# RAM_DDR3_2RANK_BGA96.net
KiCad netlist of a schematic drawn in Altium Designer
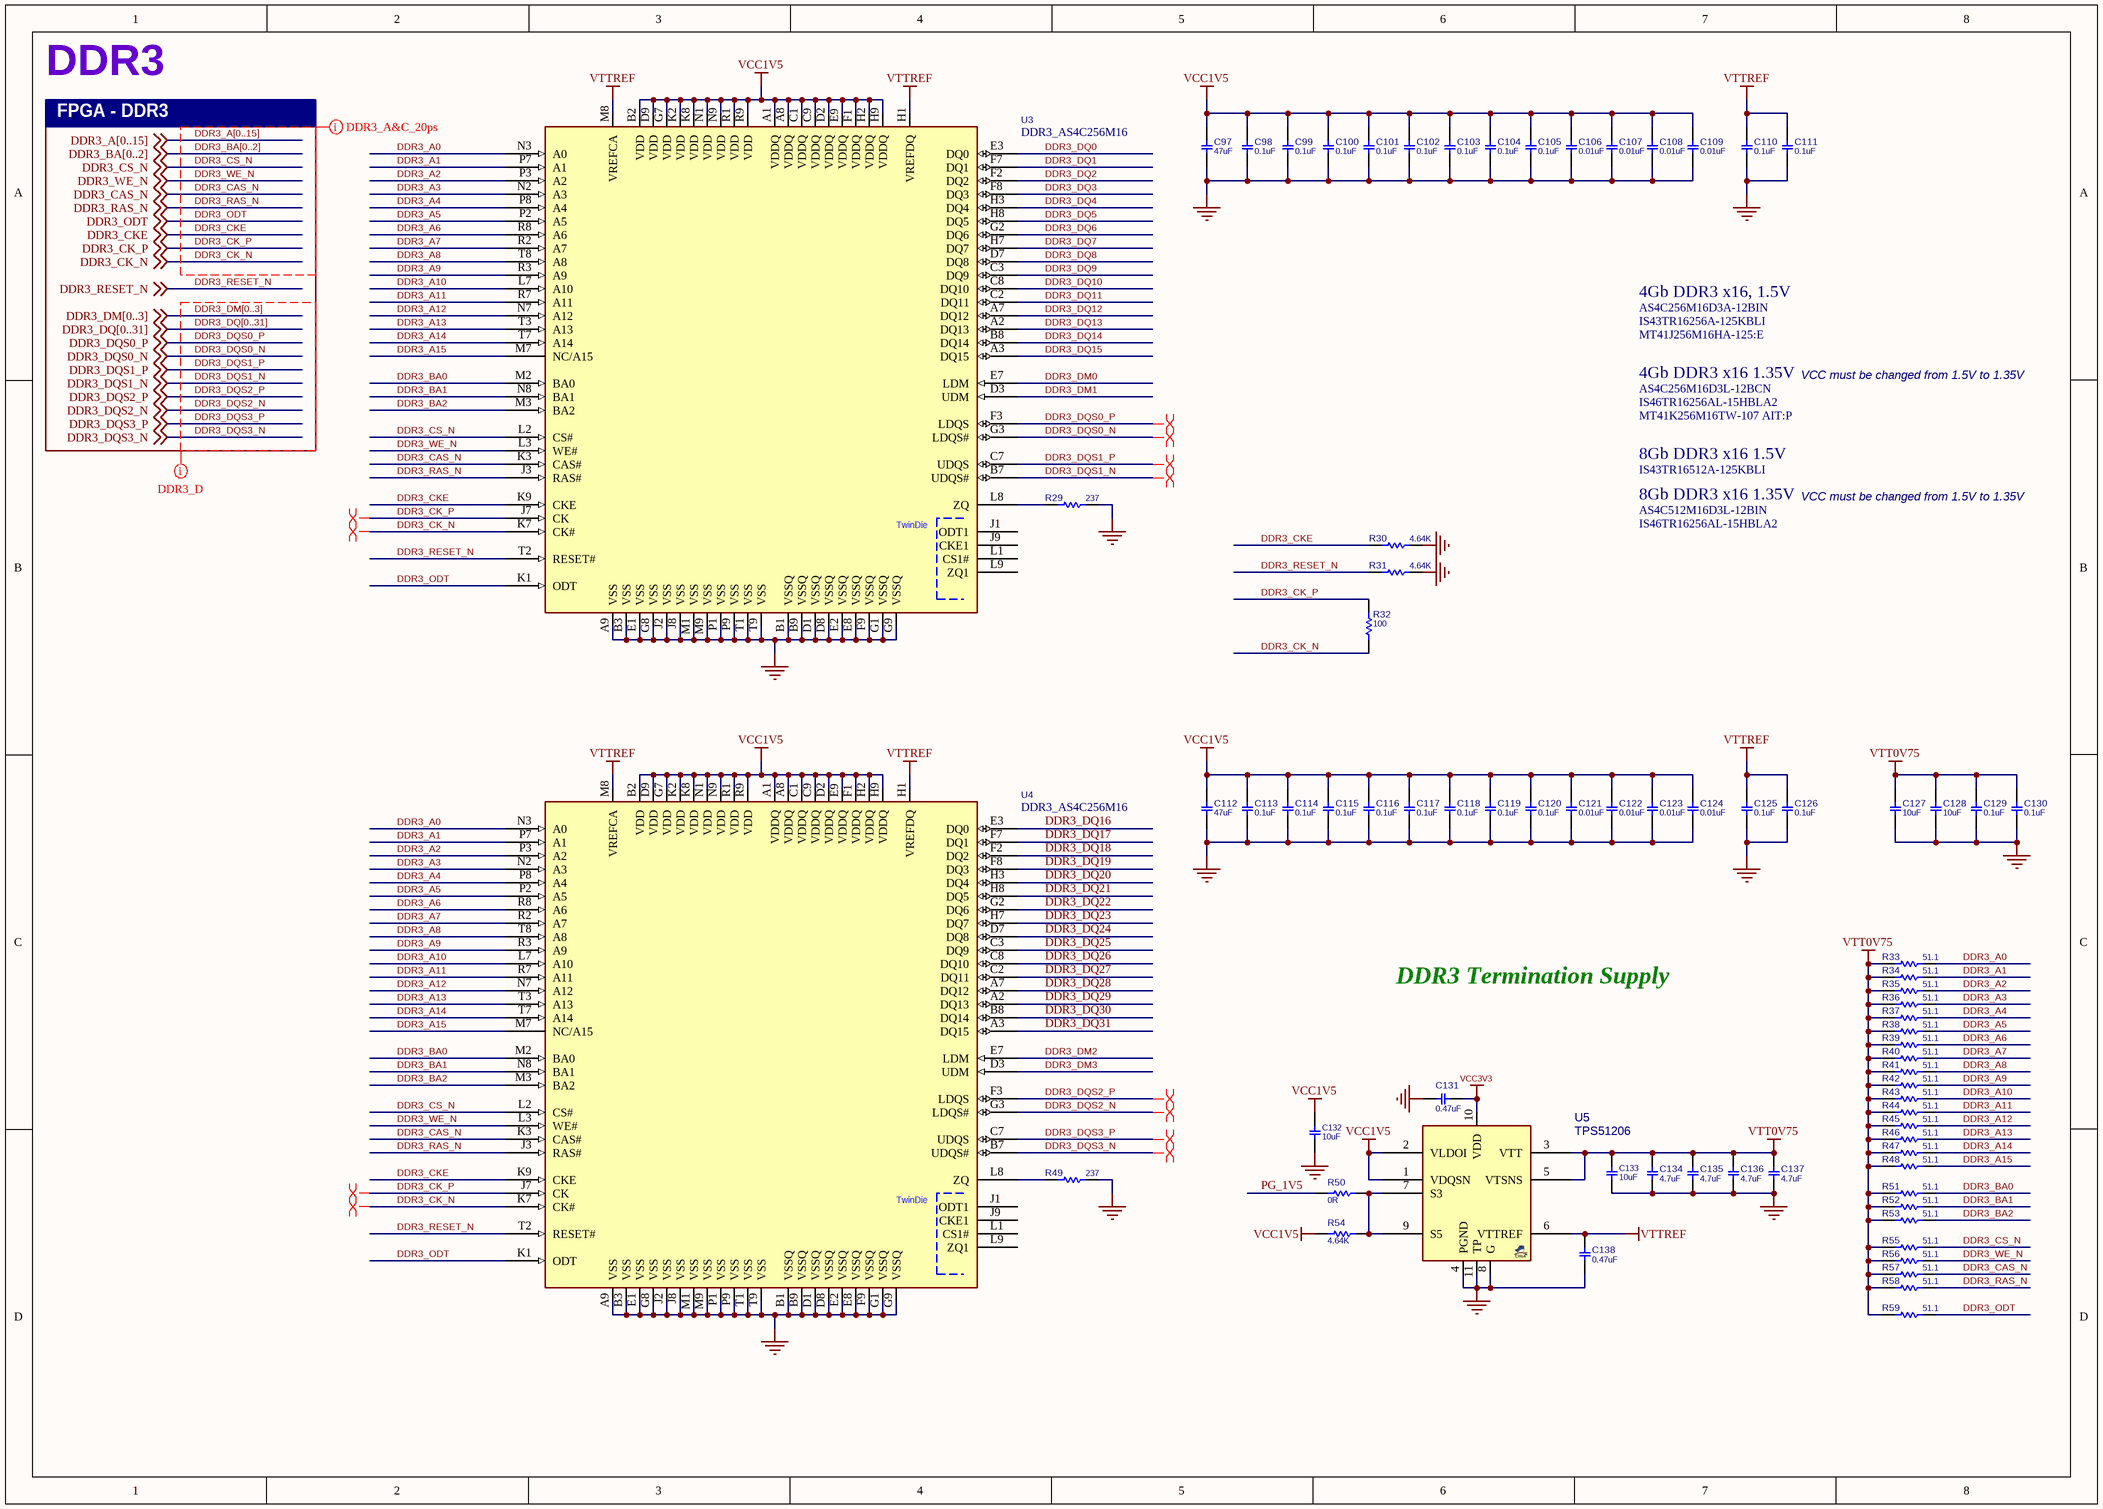
[diagram p0: RAM_DDR3_2RANK_BGA96.SchDoc]

(export (version "E")
  (design (tool "Eeschema 10.0.6"))
  (components
    (comp (ref "C97")
      (value "47uF")
      (footprint "C0805")
      (description "CAP, MLCC, X5R 47uF 16V 10% 1210")
      (fields (field (name "MANF") "Murata") (field (name "MANF_P#") "GRM32ER61C476KE15K"))
      (libsource (lib "mlcc_smd_passive") (part "CAP_SMD_MLCC_47u16V"))
    )
    (comp (ref "C98")
      (value "0.1uF")
      (footprint "C0402")
      (description "CAP, MLCC, 100nF, 50V, X7R, 10%, 0402C")
      (fields (field (name "MANF") "Taiyo Yuden") (field (name "MANF_P#") "UMK105B7104KVHF"))
      (libsource (lib "mlcc_smd_passive") (part "CAP_SMD_MLCC_100n50T"))
    )
    (comp (ref "C99")
      (value "0.1uF")
      (footprint "C0402")
      (description "CAP, MLCC, 100nF, 50V, X7R, 10%, 0402C")
      (fields (field (name "MANF") "Taiyo Yuden") (field (name "MANF_P#") "UMK105B7104KVHF"))
      (libsource (lib "mlcc_smd_passive") (part "CAP_SMD_MLCC_100n50T"))
    )
    (comp (ref "C100")
      (value "0.1uF")
      (footprint "C0402")
      (description "CAP, MLCC, 100nF, 50V, X7R, 10%, 0402C")
      (fields (field (name "MANF") "Taiyo Yuden") (field (name "MANF_P#") "UMK105B7104KVHF"))
      (libsource (lib "mlcc_smd_passive") (part "CAP_SMD_MLCC_100n50T"))
    )
    (comp (ref "C101")
      (value "0.1uF")
      (footprint "C0402")
      (description "CAP, MLCC, 100nF, 50V, X7R, 10%, 0402C")
      (fields (field (name "MANF") "Taiyo Yuden") (field (name "MANF_P#") "UMK105B7104KVHF"))
      (libsource (lib "mlcc_smd_passive") (part "CAP_SMD_MLCC_100n50T"))
    )
    (comp (ref "C102")
      (value "0.1uF")
      (footprint "C0402")
      (description "CAP, MLCC, 100nF, 50V, X7R, 10%, 0402C")
      (fields (field (name "MANF") "Taiyo Yuden") (field (name "MANF_P#") "UMK105B7104KVHF"))
      (libsource (lib "mlcc_smd_passive") (part "CAP_SMD_MLCC_100n50T"))
    )
    (comp (ref "C103")
      (value "0.1uF")
      (footprint "C0402")
      (description "CAP, MLCC, 100nF, 50V, X7R, 10%, 0402C")
      (fields (field (name "MANF") "Taiyo Yuden") (field (name "MANF_P#") "UMK105B7104KVHF"))
      (libsource (lib "mlcc_smd_passive") (part "CAP_SMD_MLCC_100n50T"))
    )
    (comp (ref "C104")
      (value "0.1uF")
      (footprint "C0402")
      (description "CAP, MLCC, 100nF, 50V, X7R, 10%, 0402C")
      (fields (field (name "MANF") "Taiyo Yuden") (field (name "MANF_P#") "UMK105B7104KVHF"))
      (libsource (lib "mlcc_smd_passive") (part "CAP_SMD_MLCC_100n50T"))
    )
    (comp (ref "C105")
      (value "0.1uF")
      (footprint "C0402")
      (description "CAP, MLCC, 100nF, 50V, X7R, 10%, 0402C")
      (fields (field (name "MANF") "Taiyo Yuden") (field (name "MANF_P#") "UMK105B7104KVHF"))
      (libsource (lib "mlcc_smd_passive") (part "CAP_SMD_MLCC_100n50T"))
    )
    (comp (ref "C106")
      (value "0.01uF")
      (footprint "C0402")
      (description "CAP, MLCC, 10nF, 50V, X7R, 10%, 0402C")
      (fields (field (name "MANF") "Murata") (field (name "MANF_P#") "GCM155R71H103KA55D"))
      (libsource (lib "chila_passive") (part "CAP_SMD_MLCC_10n50V"))
    )
    (comp (ref "C107")
      (value "0.01uF")
      (footprint "C0402")
      (description "CAP, MLCC, 10nF, 50V, X7R, 10%, 0402C")
      (fields (field (name "MANF") "Murata") (field (name "MANF_P#") "GCM155R71H103KA55D"))
      (libsource (lib "chila_passive") (part "CAP_SMD_MLCC_10n50V"))
    )
    (comp (ref "C108")
      (value "0.01uF")
      (footprint "C0402")
      (description "CAP, MLCC, 10nF, 50V, X7R, 10%, 0402C")
      (fields (field (name "MANF") "Murata") (field (name "MANF_P#") "GCM155R71H103KA55D"))
      (libsource (lib "chila_passive") (part "CAP_SMD_MLCC_10n50V"))
    )
    (comp (ref "C109")
      (value "0.01uF")
      (footprint "C0402")
      (description "CAP, MLCC, 10nF, 50V, X7R, 10%, 0402C")
      (fields (field (name "MANF") "Murata") (field (name "MANF_P#") "GCM155R71H103KA55D"))
      (libsource (lib "chila_passive") (part "CAP_SMD_MLCC_10n50V"))
    )
    (comp (ref "C110")
      (value "0.1uF")
      (footprint "C0402")
      (description "CAP, MLCC, 100nF, 50V, X7R, 10%, 0402C")
      (fields (field (name "MANF") "Taiyo Yuden") (field (name "MANF_P#") "UMK105B7104KVHF"))
      (libsource (lib "mlcc_smd_passive") (part "CAP_SMD_MLCC_100n50T"))
    )
    (comp (ref "C111")
      (value "0.1uF")
      (footprint "C0402")
      (description "CAP, MLCC, 100nF, 50V, X7R, 10%, 0402C")
      (fields (field (name "MANF") "Taiyo Yuden") (field (name "MANF_P#") "UMK105B7104KVHF"))
      (libsource (lib "mlcc_smd_passive") (part "CAP_SMD_MLCC_100n50T"))
    )
    (comp (ref "C112")
      (value "47uF")
      (footprint "C0805")
      (description "CAP, MLCC, X5R 47uF 16V 10% 1210")
      (fields (field (name "MANF") "Murata") (field (name "MANF_P#") "GRM32ER61C476KE15K"))
      (libsource (lib "mlcc_smd_passive") (part "CAP_SMD_MLCC_47u16V"))
    )
    (comp (ref "C113")
      (value "0.1uF")
      (footprint "C0402")
      (description "CAP, MLCC, 100nF, 50V, X7R, 10%, 0402C")
      (fields (field (name "MANF") "Taiyo Yuden") (field (name "MANF_P#") "UMK105B7104KVHF"))
      (libsource (lib "mlcc_smd_passive") (part "CAP_SMD_MLCC_100n50T"))
    )
    (comp (ref "C114")
      (value "0.1uF")
      (footprint "C0402")
      (description "CAP, MLCC, 100nF, 50V, X7R, 10%, 0402C")
      (fields (field (name "MANF") "Taiyo Yuden") (field (name "MANF_P#") "UMK105B7104KVHF"))
      (libsource (lib "mlcc_smd_passive") (part "CAP_SMD_MLCC_100n50T"))
    )
    (comp (ref "C115")
      (value "0.1uF")
      (footprint "C0402")
      (description "CAP, MLCC, 100nF, 50V, X7R, 10%, 0402C")
      (fields (field (name "MANF") "Taiyo Yuden") (field (name "MANF_P#") "UMK105B7104KVHF"))
      (libsource (lib "mlcc_smd_passive") (part "CAP_SMD_MLCC_100n50T"))
    )
    (comp (ref "C116")
      (value "0.1uF")
      (footprint "C0402")
      (description "CAP, MLCC, 100nF, 50V, X7R, 10%, 0402C")
      (fields (field (name "MANF") "Taiyo Yuden") (field (name "MANF_P#") "UMK105B7104KVHF"))
      (libsource (lib "mlcc_smd_passive") (part "CAP_SMD_MLCC_100n50T"))
    )
    (comp (ref "C117")
      (value "0.1uF")
      (footprint "C0402")
      (description "CAP, MLCC, 100nF, 50V, X7R, 10%, 0402C")
      (fields (field (name "MANF") "Taiyo Yuden") (field (name "MANF_P#") "UMK105B7104KVHF"))
      (libsource (lib "mlcc_smd_passive") (part "CAP_SMD_MLCC_100n50T"))
    )
    (comp (ref "C118")
      (value "0.1uF")
      (footprint "C0402")
      (description "CAP, MLCC, 100nF, 50V, X7R, 10%, 0402C")
      (fields (field (name "MANF") "Taiyo Yuden") (field (name "MANF_P#") "UMK105B7104KVHF"))
      (libsource (lib "mlcc_smd_passive") (part "CAP_SMD_MLCC_100n50T"))
    )
    (comp (ref "C119")
      (value "0.1uF")
      (footprint "C0402")
      (description "CAP, MLCC, 100nF, 50V, X7R, 10%, 0402C")
      (fields (field (name "MANF") "Taiyo Yuden") (field (name "MANF_P#") "UMK105B7104KVHF"))
      (libsource (lib "mlcc_smd_passive") (part "CAP_SMD_MLCC_100n50T"))
    )
    (comp (ref "C120")
      (value "0.1uF")
      (footprint "C0402")
      (description "CAP, MLCC, 100nF, 50V, X7R, 10%, 0402C")
      (fields (field (name "MANF") "Taiyo Yuden") (field (name "MANF_P#") "UMK105B7104KVHF"))
      (libsource (lib "mlcc_smd_passive") (part "CAP_SMD_MLCC_100n50T"))
    )
    (comp (ref "C121")
      (value "0.01uF")
      (footprint "C0402")
      (description "CAP, MLCC, 10nF, 50V, X7R, 10%, 0402C")
      (fields (field (name "MANF") "Murata") (field (name "MANF_P#") "GCM155R71H103KA55D"))
      (libsource (lib "chila_passive") (part "CAP_SMD_MLCC_10n50V"))
    )
    (comp (ref "C122")
      (value "0.01uF")
      (footprint "C0402")
      (description "CAP, MLCC, 10nF, 50V, X7R, 10%, 0402C")
      (fields (field (name "MANF") "Murata") (field (name "MANF_P#") "GCM155R71H103KA55D"))
      (libsource (lib "chila_passive") (part "CAP_SMD_MLCC_10n50V"))
    )
    (comp (ref "C123")
      (value "0.01uF")
      (footprint "C0402")
      (description "CAP, MLCC, 10nF, 50V, X7R, 10%, 0402C")
      (fields (field (name "MANF") "Murata") (field (name "MANF_P#") "GCM155R71H103KA55D"))
      (libsource (lib "chila_passive") (part "CAP_SMD_MLCC_10n50V"))
    )
    (comp (ref "C124")
      (value "0.01uF")
      (footprint "C0402")
      (description "CAP, MLCC, 10nF, 50V, X7R, 10%, 0402C")
      (fields (field (name "MANF") "Murata") (field (name "MANF_P#") "GCM155R71H103KA55D"))
      (libsource (lib "chila_passive") (part "CAP_SMD_MLCC_10n50V"))
    )
    (comp (ref "C125")
      (value "0.1uF")
      (footprint "C0402")
      (description "CAP, MLCC, 100nF, 50V, X7R, 10%, 0402C")
      (fields (field (name "MANF") "Taiyo Yuden") (field (name "MANF_P#") "UMK105B7104KVHF"))
      (libsource (lib "mlcc_smd_passive") (part "CAP_SMD_MLCC_100n50T"))
    )
    (comp (ref "C126")
      (value "0.1uF")
      (footprint "C0402")
      (description "CAP, MLCC, 100nF, 50V, X7R, 10%, 0402C")
      (fields (field (name "MANF") "Taiyo Yuden") (field (name "MANF_P#") "UMK105B7104KVHF"))
      (libsource (lib "mlcc_smd_passive") (part "CAP_SMD_MLCC_100n50T"))
    )
    (comp (ref "C127")
      (value "10uF")
      (footprint "C0603")
      (description "CAP, MLCC, 10uF, 16V, X6S, 20%, 0603")
      (fields (field (name "MANF") "Murata") (field (name "MANF_P#") "GRM188R61C106KAALD"))
      (libsource (lib "chila_passive") (part "CAP_SMD_MLCC_10u16V"))
    )
    (comp (ref "C128")
      (value "10uF")
      (footprint "C0603")
      (description "CAP, MLCC, 10uF, 16V, X6S, 20%, 0603")
      (fields (field (name "MANF") "Murata") (field (name "MANF_P#") "GRM188R61C106KAALD"))
      (libsource (lib "chila_passive") (part "CAP_SMD_MLCC_10u16V"))
    )
    (comp (ref "C129")
      (value "0.1uF")
      (footprint "C0402A")
      (description "CAP, MLCC, 100nF, 50V, X7R, 10%, 0402C")
      (fields (field (name "MANF") "Taiyo Yuden") (field (name "MANF_P#") "UMK105B7104KVHF"))
      (libsource (lib "mlcc_smd_passive") (part "CAP_SMD_MLCC_100n50T"))
    )
    (comp (ref "C130")
      (value "0.1uF")
      (footprint "C0402A")
      (description "CAP, MLCC, 100nF, 50V, X7R, 10%, 0402C")
      (fields (field (name "MANF") "Taiyo Yuden") (field (name "MANF_P#") "UMK105B7104KVHF"))
      (libsource (lib "mlcc_smd_passive") (part "CAP_SMD_MLCC_100n50T"))
    )
    (comp (ref "C131")
      (value "0.47uF")
      (footprint "C0402")
      (description "CAP, MLCC, 100nF, 50V, X7S, 5%, 0402C")
      (fields (field (name "MANF_PART#") "GRM155C71H104JE19D") (field (name "MANF") "Murata"))
      (libsource (lib "passive_mlcc_smd") (part "CAP_SMD_MLCC_100n50V"))
    )
    (comp (ref "C132")
      (value "10uF")
      (footprint "C0603")
      (description "CAP, MLCC, X5R 10uF 10% 25V 0805")
      (fields (field (name "MANF") "Taiyo Yuden") (field (name "MANF_P#") "TMK212BBJ106MG-T"))
      (libsource (lib "mlcc_smd_passive") (part "CAP_SMD_MLCC_10u25V"))
    )
    (comp (ref "C133")
      (value "10uF")
      (footprint "C0603")
      (description "CAP, MLCC, X5R 10uF 10% 25V 0805")
      (fields (field (name "MANF") "Taiyo Yuden") (field (name "MANF_P#") "TMK212BBJ106MG-T"))
      (libsource (lib "mlcc_smd_passive") (part "CAP_SMD_MLCC_10u25V"))
    )
    (comp (ref "C134")
      (value "4.7uF")
      (footprint "C0603")
      (description "CAP, MLCC, 100nF, 50V, X7S, 5%, 0402C")
      (fields (field (name "MANF_PART#") "GRM155C71H104JE19D") (field (name "MANF") "Murata"))
      (libsource (lib "passive_mlcc_smd") (part "CAP_SMD_MLCC_100n50V"))
    )
    (comp (ref "C135")
      (value "4.7uF")
      (footprint "C0603")
      (description "CAP, MLCC, 100nF, 50V, X7S, 5%, 0402C")
      (fields (field (name "MANF_PART#") "GRM155C71H104JE19D") (field (name "MANF") "Murata"))
      (libsource (lib "passive_mlcc_smd") (part "CAP_SMD_MLCC_100n50V"))
    )
    (comp (ref "C136")
      (value "4.7uF")
      (footprint "C0603")
      (description "CAP, MLCC, 100nF, 50V, X7S, 5%, 0402C")
      (fields (field (name "MANF_PART#") "GRM155C71H104JE19D") (field (name "MANF") "Murata"))
      (libsource (lib "passive_mlcc_smd") (part "CAP_SMD_MLCC_100n50V"))
    )
    (comp (ref "C137")
      (value "4.7uF")
      (footprint "C0603")
      (description "CAP, MLCC, 100nF, 50V, X7S, 5%, 0402C")
      (fields (field (name "MANF_PART#") "GRM155C71H104JE19D") (field (name "MANF") "Murata"))
      (libsource (lib "passive_mlcc_smd") (part "CAP_SMD_MLCC_100n50V"))
    )
    (comp (ref "C138")
      (value "0.47uF")
      (footprint "C0402")
      (description "CAP, MLCC, 100nF, 50V, X7S, 5%, 0402C")
      (fields (field (name "MANF_PART#") "GRM155C71H104JE19D") (field (name "MANF") "Murata"))
      (libsource (lib "passive_mlcc_smd") (part "CAP_SMD_MLCC_100n50V"))
    )
    (comp (ref "R29")
      (value "237")
      (footprint "R0402")
      (description "RESISTOR, SMD")
      (fields (field (name "MANF") "KOA SPEER") (field (name "MANF_P#") "RK73H1ETTP2400F"))
      (libsource (lib "chila_passive") (part "RES_SMD"))
    )
    (comp (ref "R30")
      (value "4.64K")
      (footprint "R0402")
      (description "RESISTOR, SMD")
      (fields (field (name "MANF") "Yageo") (field (name "MANF_P#") "RC0402FR-074K7L"))
      (libsource (lib "chila_passive") (part "RES_SMD"))
    )
    (comp (ref "R31")
      (value "4.64K")
      (footprint "R0402")
      (description "RESISTOR, SMD")
      (fields (field (name "MANF") "Yageo") (field (name "MANF_P#") "RC0402FR-074K7L"))
      (libsource (lib "chila_passive") (part "RES_SMD"))
    )
    (comp (ref "R32")
      (value "100")
      (footprint "R0402A")
      (description "RESISTOR, SMD")
      (fields (field (name "MANF") "Yageo") (field (name "MANF_P#") "RC0402FR-13100RL"))
      (libsource (lib "chila_passive") (part "RES_SMD"))
    )
    (comp (ref "R33")
      (value "51.1")
      (footprint "R0402A")
      (description "RESISTOR, SMD")
      (fields (field (name "MANF") "Yageo") (field (name "MANF_P#") "RC0402FR-074K7L"))
      (libsource (lib "chila_passive") (part "RES_SMD"))
    )
    (comp (ref "R34")
      (value "51.1")
      (footprint "R0402A")
      (description "RESISTOR, SMD")
      (fields (field (name "MANF") "Yageo") (field (name "MANF_P#") "RC0402FR-074K7L"))
      (libsource (lib "chila_passive") (part "RES_SMD"))
    )
    (comp (ref "R35")
      (value "51.1")
      (footprint "R0402A")
      (description "RESISTOR, SMD")
      (fields (field (name "MANF") "Yageo") (field (name "MANF_P#") "RC0402FR-074K7L"))
      (libsource (lib "chila_passive") (part "RES_SMD"))
    )
    (comp (ref "R36")
      (value "51.1")
      (footprint "R0402A")
      (description "RESISTOR, SMD")
      (fields (field (name "MANF") "Yageo") (field (name "MANF_P#") "RC0402FR-074K7L"))
      (libsource (lib "chila_passive") (part "RES_SMD"))
    )
    (comp (ref "R37")
      (value "51.1")
      (footprint "R0402A")
      (description "RESISTOR, SMD")
      (fields (field (name "MANF") "Yageo") (field (name "MANF_P#") "RC0402FR-074K7L"))
      (libsource (lib "chila_passive") (part "RES_SMD"))
    )
    (comp (ref "R38")
      (value "51.1")
      (footprint "R0402A")
      (description "RESISTOR, SMD")
      (fields (field (name "MANF") "Yageo") (field (name "MANF_P#") "RC0402FR-074K7L"))
      (libsource (lib "chila_passive") (part "RES_SMD"))
    )
    (comp (ref "R39")
      (value "51.1")
      (footprint "R0402A")
      (description "RESISTOR, SMD")
      (fields (field (name "MANF") "Yageo") (field (name "MANF_P#") "RC0402FR-074K7L"))
      (libsource (lib "chila_passive") (part "RES_SMD"))
    )
    (comp (ref "R40")
      (value "51.1")
      (footprint "R0402A")
      (description "RESISTOR, SMD")
      (fields (field (name "MANF") "Yageo") (field (name "MANF_P#") "RC0402FR-074K7L"))
      (libsource (lib "chila_passive") (part "RES_SMD"))
    )
    (comp (ref "R41")
      (value "51.1")
      (footprint "R0402A")
      (description "RESISTOR, SMD")
      (fields (field (name "MANF") "Yageo") (field (name "MANF_P#") "RC0402FR-074K7L"))
      (libsource (lib "chila_passive") (part "RES_SMD"))
    )
    (comp (ref "R42")
      (value "51.1")
      (footprint "R0402A")
      (description "RESISTOR, SMD")
      (fields (field (name "MANF") "Yageo") (field (name "MANF_P#") "RC0402FR-074K7L"))
      (libsource (lib "chila_passive") (part "RES_SMD"))
    )
    (comp (ref "R43")
      (value "51.1")
      (footprint "R0402A")
      (description "RESISTOR, SMD")
      (fields (field (name "MANF") "Yageo") (field (name "MANF_P#") "RC0402FR-074K7L"))
      (libsource (lib "chila_passive") (part "RES_SMD"))
    )
    (comp (ref "R44")
      (value "51.1")
      (footprint "R0402A")
      (description "RESISTOR, SMD")
      (fields (field (name "MANF") "Yageo") (field (name "MANF_P#") "RC0402FR-074K7L"))
      (libsource (lib "chila_passive") (part "RES_SMD"))
    )
    (comp (ref "R45")
      (value "51.1")
      (footprint "R0402A")
      (description "RESISTOR, SMD")
      (fields (field (name "MANF") "Yageo") (field (name "MANF_P#") "RC0402FR-074K7L"))
      (libsource (lib "chila_passive") (part "RES_SMD"))
    )
    (comp (ref "R46")
      (value "51.1")
      (footprint "R0402A")
      (description "RESISTOR, SMD")
      (fields (field (name "MANF") "Yageo") (field (name "MANF_P#") "RC0402FR-074K7L"))
      (libsource (lib "chila_passive") (part "RES_SMD"))
    )
    (comp (ref "R47")
      (value "51.1")
      (footprint "R0402A")
      (description "RESISTOR, SMD")
      (fields (field (name "MANF") "Yageo") (field (name "MANF_P#") "RC0402FR-074K7L"))
      (libsource (lib "chila_passive") (part "RES_SMD"))
    )
    (comp (ref "R48")
      (value "51.1")
      (footprint "R0402A")
      (description "RESISTOR, SMD")
      (fields (field (name "MANF") "Yageo") (field (name "MANF_P#") "RC0402FR-074K7L"))
      (libsource (lib "chila_passive") (part "RES_SMD"))
    )
    (comp (ref "R49")
      (value "237")
      (footprint "R0402")
      (description "RESISTOR, SMD")
      (fields (field (name "MANF") "KOA SPEER") (field (name "MANF_P#") "RK73H1ETTP2400F"))
      (libsource (lib "chila_passive") (part "RES_SMD"))
    )
    (comp (ref "R50")
      (value "0R")
      (footprint "R0402")
      (description "RESISTOR, SMD, 10K, 1%, 0402")
      (fields (field (name "MANF") "KOA SPEER") (field (name "MANF_P#") "RK73H1ETTP1002F"))
      (libsource (lib "chila_passive") (part "RES_SMD"))
    )
    (comp (ref "R51")
      (value "51.1")
      (footprint "R0402A")
      (description "RESISTOR, SMD")
      (fields (field (name "MANF") "Yageo") (field (name "MANF_P#") "RC0402FR-074K7L"))
      (libsource (lib "chila_passive") (part "RES_SMD"))
    )
    (comp (ref "R52")
      (value "51.1")
      (footprint "R0402A")
      (description "RESISTOR, SMD")
      (fields (field (name "MANF") "Yageo") (field (name "MANF_P#") "RC0402FR-074K7L"))
      (libsource (lib "chila_passive") (part "RES_SMD"))
    )
    (comp (ref "R53")
      (value "51.1")
      (footprint "R0402A")
      (description "RESISTOR, SMD")
      (fields (field (name "MANF") "Yageo") (field (name "MANF_P#") "RC0402FR-074K7L"))
      (libsource (lib "chila_passive") (part "RES_SMD"))
    )
    (comp (ref "R54")
      (value "4.64K")
      (footprint "R0402")
      (description "RESISTOR, SMD, 10K, 1%, 0402")
      (fields (field (name "MANF") "KOA SPEER") (field (name "MANF_P#") "RK73H1ETTP1002F"))
      (libsource (lib "chila_passive") (part "RES_SMD"))
    )
    (comp (ref "R55")
      (value "51.1")
      (footprint "R0402A")
      (description "RESISTOR, SMD")
      (fields (field (name "MANF") "Yageo") (field (name "MANF_P#") "RC0402FR-074K7L"))
      (libsource (lib "chila_passive") (part "RES_SMD"))
    )
    (comp (ref "R56")
      (value "51.1")
      (footprint "R0402A")
      (description "RESISTOR, SMD")
      (fields (field (name "MANF") "Yageo") (field (name "MANF_P#") "RC0402FR-074K7L"))
      (libsource (lib "chila_passive") (part "RES_SMD"))
    )
    (comp (ref "R57")
      (value "51.1")
      (footprint "R0402A")
      (description "RESISTOR, SMD")
      (fields (field (name "MANF") "Yageo") (field (name "MANF_P#") "RC0402FR-074K7L"))
      (libsource (lib "chila_passive") (part "RES_SMD"))
    )
    (comp (ref "R58")
      (value "51.1")
      (footprint "R0402A")
      (description "RESISTOR, SMD")
      (fields (field (name "MANF") "Yageo") (field (name "MANF_P#") "RC0402FR-074K7L"))
      (libsource (lib "chila_passive") (part "RES_SMD"))
    )
    (comp (ref "R59")
      (value "51.1")
      (footprint "R0402A")
      (description "RESISTOR, SMD")
      (fields (field (name "MANF") "Yageo") (field (name "MANF_P#") "RC0402FR-074K7L"))
      (libsource (lib "chila_passive") (part "RES_SMD"))
    )
    (comp (ref "U3")
      (value "DDR3_AS4C256M16")
      (footprint "BGA80_96_9X16B")
      (description "DDR3L SDRAM, 4Gb (256Mb X16), 1.5V, FBGA-96")
      (fields (field (name "MANF") "ALLIANCE MEMORY") (field (name "MANF_P#") "AS4C256M16D3A-12BIN"))
      (libsource (lib "PX7KAN01") (part "DDR3_AS4C256M16_BGA96"))
    )
    (comp (ref "U4")
      (value "DDR3_AS4C256M16")
      (footprint "BGA80_96_9X16B")
      (description "DDR3L SDRAM, 4Gb (256Mb X16), 1.5V, FBGA-96")
      (fields (field (name "MANF") "ALLIANCE MEMORY") (field (name "MANF_P#") "AS4C256M16D3A-12BIN"))
      (libsource (lib "PX7KAN01") (part "DDR3_AS4C256M16_BGA96"))
    )
    (comp (ref "U5")
      (value "TPS51206")
      (footprint "SON40_10T_2020")
      (description "REG, Linear, LDO, 2A Sink/Source DDR Termination, SON-10")
      (fields (field (name "MANF") "TI") (field (name "MANF_P#") "TPS51206DSQ"))
      (libsource (lib "reg_DDR") (part "VREG_TPS51206_SON10"))
    )
  )
  (nets
    (net (code "1") (name "/PG_1V5") (class "Default")
      (node (ref "R50") (pin "1") (pinfunction "1_1") (pintype "passive"))
    )
    (net (code "2") (name "DDR3_A0") (class "Default")
      (node (ref "R33") (pin "2") (pinfunction "2_2") (pintype "passive"))
      (node (ref "U3") (pin "N3") (pinfunction "A0_N3") (pintype "input"))
      (node (ref "U4") (pin "N3") (pinfunction "A0_N3") (pintype "input"))
    )
    (net (code "3") (name "DDR3_A1") (class "Default")
      (node (ref "R34") (pin "2") (pinfunction "2_2") (pintype "passive"))
      (node (ref "U3") (pin "P7") (pinfunction "A1_P7") (pintype "input"))
      (node (ref "U4") (pin "P7") (pinfunction "A1_P7") (pintype "input"))
    )
    (net (code "4") (name "DDR3_A2") (class "Default")
      (node (ref "R35") (pin "2") (pinfunction "2_2") (pintype "passive"))
      (node (ref "U3") (pin "P3") (pinfunction "A2_P3") (pintype "input"))
      (node (ref "U4") (pin "P3") (pinfunction "A2_P3") (pintype "input"))
    )
    (net (code "5") (name "DDR3_A3") (class "Default")
      (node (ref "R36") (pin "2") (pinfunction "2_2") (pintype "passive"))
      (node (ref "U3") (pin "N2") (pinfunction "A3_N2") (pintype "input"))
      (node (ref "U4") (pin "N2") (pinfunction "A3_N2") (pintype "input"))
    )
    (net (code "6") (name "DDR3_A4") (class "Default")
      (node (ref "R37") (pin "2") (pinfunction "2_2") (pintype "passive"))
      (node (ref "U3") (pin "P8") (pinfunction "A4_P8") (pintype "input"))
      (node (ref "U4") (pin "P8") (pinfunction "A4_P8") (pintype "input"))
    )
    (net (code "7") (name "DDR3_A5") (class "Default")
      (node (ref "R38") (pin "2") (pinfunction "2_2") (pintype "passive"))
      (node (ref "U3") (pin "P2") (pinfunction "A5_P2") (pintype "input"))
      (node (ref "U4") (pin "P2") (pinfunction "A5_P2") (pintype "input"))
    )
    (net (code "8") (name "DDR3_A6") (class "Default")
      (node (ref "R39") (pin "2") (pinfunction "2_2") (pintype "passive"))
      (node (ref "U3") (pin "R8") (pinfunction "A6_R8") (pintype "input"))
      (node (ref "U4") (pin "R8") (pinfunction "A6_R8") (pintype "input"))
    )
    (net (code "9") (name "DDR3_A7") (class "Default")
      (node (ref "R40") (pin "2") (pinfunction "2_2") (pintype "passive"))
      (node (ref "U3") (pin "R2") (pinfunction "A7_R2") (pintype "input"))
      (node (ref "U4") (pin "R2") (pinfunction "A7_R2") (pintype "input"))
    )
    (net (code "10") (name "DDR3_A8") (class "Default")
      (node (ref "R41") (pin "2") (pinfunction "2_2") (pintype "passive"))
      (node (ref "U3") (pin "T8") (pinfunction "A8_T8") (pintype "input"))
      (node (ref "U4") (pin "T8") (pinfunction "A8_T8") (pintype "input"))
    )
    (net (code "11") (name "DDR3_A9") (class "Default")
      (node (ref "R42") (pin "2") (pinfunction "2_2") (pintype "passive"))
      (node (ref "U3") (pin "R3") (pinfunction "A9_R3") (pintype "input"))
      (node (ref "U4") (pin "R3") (pinfunction "A9_R3") (pintype "input"))
    )
    (net (code "12") (name "DDR3_A10") (class "Default")
      (node (ref "R43") (pin "2") (pinfunction "2_2") (pintype "passive"))
      (node (ref "U3") (pin "L7") (pinfunction "A10_L7") (pintype "input"))
      (node (ref "U4") (pin "L7") (pinfunction "A10_L7") (pintype "input"))
    )
    (net (code "13") (name "DDR3_A11") (class "Default")
      (node (ref "R44") (pin "2") (pinfunction "2_2") (pintype "passive"))
      (node (ref "U3") (pin "R7") (pinfunction "A11_R7") (pintype "input"))
      (node (ref "U4") (pin "R7") (pinfunction "A11_R7") (pintype "input"))
    )
    (net (code "14") (name "DDR3_A12") (class "Default")
      (node (ref "R45") (pin "2") (pinfunction "2_2") (pintype "passive"))
      (node (ref "U3") (pin "N7") (pinfunction "A12_N7") (pintype "input"))
      (node (ref "U4") (pin "N7") (pinfunction "A12_N7") (pintype "input"))
    )
    (net (code "15") (name "DDR3_A13") (class "Default")
      (node (ref "R46") (pin "2") (pinfunction "2_2") (pintype "passive"))
      (node (ref "U3") (pin "T3") (pinfunction "A13_T3") (pintype "input"))
      (node (ref "U4") (pin "T3") (pinfunction "A13_T3") (pintype "input"))
    )
    (net (code "16") (name "DDR3_A14") (class "Default")
      (node (ref "R47") (pin "2") (pinfunction "2_2") (pintype "passive"))
      (node (ref "U3") (pin "T7") (pinfunction "A14_T7") (pintype "input"))
      (node (ref "U4") (pin "T7") (pinfunction "A14_T7") (pintype "input"))
    )
    (net (code "17") (name "DDR3_A15") (class "Default")
      (node (ref "R48") (pin "2") (pinfunction "2_2") (pintype "passive"))
      (node (ref "U3") (pin "M7") (pinfunction "NC/A15_M7") (pintype "passive"))
      (node (ref "U4") (pin "M7") (pinfunction "NC/A15_M7") (pintype "passive"))
    )
    (net (code "19") (name "DDR3_BA0") (class "Default")
      (node (ref "R51") (pin "2") (pinfunction "2_2") (pintype "passive"))
      (node (ref "U3") (pin "M2") (pinfunction "BA0_M2") (pintype "input"))
      (node (ref "U4") (pin "M2") (pinfunction "BA0_M2") (pintype "input"))
    )
    (net (code "20") (name "DDR3_BA1") (class "Default")
      (node (ref "R52") (pin "2") (pinfunction "2_2") (pintype "passive"))
      (node (ref "U3") (pin "N8") (pinfunction "BA1_N8") (pintype "input"))
      (node (ref "U4") (pin "N8") (pinfunction "BA1_N8") (pintype "input"))
    )
    (net (code "21") (name "DDR3_BA2") (class "Default")
      (node (ref "R53") (pin "2") (pinfunction "2_2") (pintype "passive"))
      (node (ref "U3") (pin "M3") (pinfunction "BA2_M3") (pintype "input"))
      (node (ref "U4") (pin "M3") (pinfunction "BA2_M3") (pintype "input"))
    )
    (net (code "23") (name "DDR3_CAS_N") (class "Default")
      (node (ref "R57") (pin "2") (pinfunction "2_2") (pintype "passive"))
      (node (ref "U3") (pin "K3") (pinfunction "CAS#_K3") (pintype "input"))
      (node (ref "U4") (pin "K3") (pinfunction "CAS#_K3") (pintype "input"))
    )
    (net (code "24") (name "DDR3_CKE") (class "Default")
      (node (ref "R30") (pin "1") (pinfunction "1_1") (pintype "passive"))
      (node (ref "U3") (pin "K9") (pinfunction "CKE_K9") (pintype "input"))
      (node (ref "U4") (pin "K9") (pinfunction "CKE_K9") (pintype "input"))
    )
    (net (code "25") (name "DDR3_CK_N") (class "Default")
      (node (ref "R32") (pin "1") (pinfunction "1_1") (pintype "passive"))
      (node (ref "U3") (pin "K7") (pinfunction "CK#_K7") (pintype "input"))
      (node (ref "U4") (pin "K7") (pinfunction "CK#_K7") (pintype "input"))
    )
    (net (code "26") (name "DDR3_CK_P") (class "Default")
      (node (ref "R32") (pin "2") (pinfunction "2_2") (pintype "passive"))
      (node (ref "U3") (pin "J7") (pinfunction "CK_J7") (pintype "input"))
      (node (ref "U4") (pin "J7") (pinfunction "CK_J7") (pintype "input"))
    )
    (net (code "27") (name "DDR3_CS_N") (class "Default")
      (node (ref "R55") (pin "2") (pinfunction "2_2") (pintype "passive"))
      (node (ref "U3") (pin "L2") (pinfunction "CS#_L2") (pintype "input"))
      (node (ref "U4") (pin "L2") (pinfunction "CS#_L2") (pintype "input"))
    )
    (net (code "28") (name "DDR3_DM0") (class "Default")
      (node (ref "U3") (pin "E7") (pinfunction "LDM_E7") (pintype "input"))
    )
    (net (code "29") (name "DDR3_DM1") (class "Default")
      (node (ref "U3") (pin "D3") (pinfunction "UDM_D3") (pintype "input"))
    )
    (net (code "30") (name "DDR3_DM2") (class "Default")
      (node (ref "U4") (pin "E7") (pinfunction "LDM_E7") (pintype "input"))
    )
    (net (code "31") (name "DDR3_DM3") (class "Default")
      (node (ref "U4") (pin "D3") (pinfunction "UDM_D3") (pintype "input"))
    )
    (net (code "33") (name "DDR3_DQ0") (class "Default")
      (node (ref "U3") (pin "E3") (pinfunction "DQ0_E3") (pintype "bidirectional"))
    )
    (net (code "34") (name "DDR3_DQ1") (class "Default")
      (node (ref "U3") (pin "F7") (pinfunction "DQ1_F7") (pintype "bidirectional"))
    )
    (net (code "35") (name "DDR3_DQ2") (class "Default")
      (node (ref "U3") (pin "F2") (pinfunction "DQ2_F2") (pintype "bidirectional"))
    )
    (net (code "36") (name "DDR3_DQ3") (class "Default")
      (node (ref "U3") (pin "F8") (pinfunction "DQ3_F8") (pintype "bidirectional"))
    )
    (net (code "37") (name "DDR3_DQ4") (class "Default")
      (node (ref "U3") (pin "H3") (pinfunction "DQ4_H3") (pintype "bidirectional"))
    )
    (net (code "38") (name "DDR3_DQ5") (class "Default")
      (node (ref "U3") (pin "H8") (pinfunction "DQ5_H8") (pintype "bidirectional"))
    )
    (net (code "39") (name "DDR3_DQ6") (class "Default")
      (node (ref "U3") (pin "G2") (pinfunction "DQ6_G2") (pintype "bidirectional"))
    )
    (net (code "40") (name "DDR3_DQ7") (class "Default")
      (node (ref "U3") (pin "H7") (pinfunction "DQ7_H7") (pintype "bidirectional"))
    )
    (net (code "41") (name "DDR3_DQ8") (class "Default")
      (node (ref "U3") (pin "D7") (pinfunction "DQ8_D7") (pintype "bidirectional"))
    )
    (net (code "42") (name "DDR3_DQ9") (class "Default")
      (node (ref "U3") (pin "C3") (pinfunction "DQ9_C3") (pintype "bidirectional"))
    )
    (net (code "43") (name "DDR3_DQ10") (class "Default")
      (node (ref "U3") (pin "C8") (pinfunction "DQ10_C8") (pintype "bidirectional"))
    )
    (net (code "44") (name "DDR3_DQ11") (class "Default")
      (node (ref "U3") (pin "C2") (pinfunction "DQ11_C2") (pintype "bidirectional"))
    )
    (net (code "45") (name "DDR3_DQ12") (class "Default")
      (node (ref "U3") (pin "A7") (pinfunction "DQ12_A7") (pintype "bidirectional"))
    )
    (net (code "46") (name "DDR3_DQ13") (class "Default")
      (node (ref "U3") (pin "A2") (pinfunction "DQ13_A2") (pintype "bidirectional"))
    )
    (net (code "47") (name "DDR3_DQ14") (class "Default")
      (node (ref "U3") (pin "B8") (pinfunction "DQ14_B8") (pintype "bidirectional"))
    )
    (net (code "48") (name "DDR3_DQ15") (class "Default")
      (node (ref "U3") (pin "A3") (pinfunction "DQ15_A3") (pintype "bidirectional"))
    )
    (net (code "49") (name "DDR3_DQ16") (class "Default")
      (node (ref "U4") (pin "E3") (pinfunction "DQ0_E3") (pintype "bidirectional"))
    )
    (net (code "50") (name "DDR3_DQ17") (class "Default")
      (node (ref "U4") (pin "F7") (pinfunction "DQ1_F7") (pintype "bidirectional"))
    )
    (net (code "51") (name "DDR3_DQ18") (class "Default")
      (node (ref "U4") (pin "F2") (pinfunction "DQ2_F2") (pintype "bidirectional"))
    )
    (net (code "52") (name "DDR3_DQ19") (class "Default")
      (node (ref "U4") (pin "F8") (pinfunction "DQ3_F8") (pintype "bidirectional"))
    )
    (net (code "53") (name "DDR3_DQ20") (class "Default")
      (node (ref "U4") (pin "H3") (pinfunction "DQ4_H3") (pintype "bidirectional"))
    )
    (net (code "54") (name "DDR3_DQ21") (class "Default")
      (node (ref "U4") (pin "H8") (pinfunction "DQ5_H8") (pintype "bidirectional"))
    )
    (net (code "55") (name "DDR3_DQ22") (class "Default")
      (node (ref "U4") (pin "G2") (pinfunction "DQ6_G2") (pintype "bidirectional"))
    )
    (net (code "56") (name "DDR3_DQ23") (class "Default")
      (node (ref "U4") (pin "H7") (pinfunction "DQ7_H7") (pintype "bidirectional"))
    )
    (net (code "57") (name "DDR3_DQ24") (class "Default")
      (node (ref "U4") (pin "D7") (pinfunction "DQ8_D7") (pintype "bidirectional"))
    )
    (net (code "58") (name "DDR3_DQ25") (class "Default")
      (node (ref "U4") (pin "C3") (pinfunction "DQ9_C3") (pintype "bidirectional"))
    )
    (net (code "59") (name "DDR3_DQ26") (class "Default")
      (node (ref "U4") (pin "C8") (pinfunction "DQ10_C8") (pintype "bidirectional"))
    )
    (net (code "60") (name "DDR3_DQ27") (class "Default")
      (node (ref "U4") (pin "C2") (pinfunction "DQ11_C2") (pintype "bidirectional"))
    )
    (net (code "61") (name "DDR3_DQ28") (class "Default")
      (node (ref "U4") (pin "A7") (pinfunction "DQ12_A7") (pintype "bidirectional"))
    )
    (net (code "62") (name "DDR3_DQ29") (class "Default")
      (node (ref "U4") (pin "A2") (pinfunction "DQ13_A2") (pintype "bidirectional"))
    )
    (net (code "63") (name "DDR3_DQ30") (class "Default")
      (node (ref "U4") (pin "B8") (pinfunction "DQ14_B8") (pintype "bidirectional"))
    )
    (net (code "64") (name "DDR3_DQ31") (class "Default")
      (node (ref "U4") (pin "A3") (pinfunction "DQ15_A3") (pintype "bidirectional"))
    )
    (net (code "65") (name "DDR3_DQS0_N") (class "Default")
      (node (ref "U3") (pin "G3") (pinfunction "LDQS#_G3") (pintype "bidirectional"))
    )
    (net (code "66") (name "DDR3_DQS0_P") (class "Default")
      (node (ref "U3") (pin "F3") (pinfunction "LDQS_F3") (pintype "bidirectional"))
    )
    (net (code "67") (name "DDR3_DQS1_N") (class "Default")
      (node (ref "U3") (pin "B7") (pinfunction "UDQS#_B7") (pintype "bidirectional"))
    )
    (net (code "68") (name "DDR3_DQS1_P") (class "Default")
      (node (ref "U3") (pin "C7") (pinfunction "UDQS_C7") (pintype "bidirectional"))
    )
    (net (code "69") (name "DDR3_DQS2_N") (class "Default")
      (node (ref "U4") (pin "G3") (pinfunction "LDQS#_G3") (pintype "bidirectional"))
    )
    (net (code "70") (name "DDR3_DQS2_P") (class "Default")
      (node (ref "U4") (pin "F3") (pinfunction "LDQS_F3") (pintype "bidirectional"))
    )
    (net (code "71") (name "DDR3_DQS3_N") (class "Default")
      (node (ref "U4") (pin "B7") (pinfunction "UDQS#_B7") (pintype "bidirectional"))
    )
    (net (code "72") (name "DDR3_DQS3_P") (class "Default")
      (node (ref "U4") (pin "C7") (pinfunction "UDQS_C7") (pintype "bidirectional"))
    )
    (net (code "74") (name "DDR3_ODT") (class "Default")
      (node (ref "R59") (pin "2") (pinfunction "2_2") (pintype "passive"))
      (node (ref "U3") (pin "K1") (pinfunction "ODT_K1") (pintype "input"))
      (node (ref "U4") (pin "K1") (pinfunction "ODT_K1") (pintype "input"))
    )
    (net (code "75") (name "DDR3_RAS_N") (class "Default")
      (node (ref "R58") (pin "2") (pinfunction "2_2") (pintype "passive"))
      (node (ref "U3") (pin "J3") (pinfunction "RAS#_J3") (pintype "input"))
      (node (ref "U4") (pin "J3") (pinfunction "RAS#_J3") (pintype "input"))
    )
    (net (code "76") (name "DDR3_RESET_N") (class "Default")
      (node (ref "R31") (pin "1") (pinfunction "1_1") (pintype "passive"))
      (node (ref "U3") (pin "T2") (pinfunction "RESET#_T2") (pintype "input"))
      (node (ref "U4") (pin "T2") (pinfunction "RESET#_T2") (pintype "input"))
    )
    (net (code "77") (name "DDR3_WE_N") (class "Default")
      (node (ref "R56") (pin "2") (pinfunction "2_2") (pintype "passive"))
      (node (ref "U3") (pin "L3") (pinfunction "WE#_L3") (pintype "input"))
      (node (ref "U4") (pin "L3") (pinfunction "WE#_L3") (pintype "input"))
    )
    (net (code "78") (name "GND") (class "Default")
      (node (ref "C100") (pin "1") (pinfunction "1_1") (pintype "passive"))
      (node (ref "C101") (pin "1") (pinfunction "1_1") (pintype "passive"))
      (node (ref "C102") (pin "1") (pinfunction "1_1") (pintype "passive"))
      (node (ref "C103") (pin "1") (pinfunction "1_1") (pintype "passive"))
      (node (ref "C104") (pin "1") (pinfunction "1_1") (pintype "passive"))
      (node (ref "C105") (pin "1") (pinfunction "1_1") (pintype "passive"))
      (node (ref "C106") (pin "1") (pinfunction "1_1") (pintype "passive"))
      (node (ref "C107") (pin "1") (pinfunction "1_1") (pintype "passive"))
      (node (ref "C108") (pin "1") (pinfunction "1_1") (pintype "passive"))
      (node (ref "C109") (pin "1") (pinfunction "1_1") (pintype "passive"))
      (node (ref "C110") (pin "1") (pinfunction "1_1") (pintype "passive"))
      (node (ref "C111") (pin "1") (pinfunction "1_1") (pintype "passive"))
      (node (ref "C112") (pin "1") (pinfunction "1_1") (pintype "passive"))
      (node (ref "C113") (pin "1") (pinfunction "1_1") (pintype "passive"))
      (node (ref "C114") (pin "1") (pinfunction "1_1") (pintype "passive"))
      (node (ref "C115") (pin "1") (pinfunction "1_1") (pintype "passive"))
      (node (ref "C116") (pin "1") (pinfunction "1_1") (pintype "passive"))
      (node (ref "C117") (pin "1") (pinfunction "1_1") (pintype "passive"))
      (node (ref "C118") (pin "1") (pinfunction "1_1") (pintype "passive"))
      (node (ref "C119") (pin "1") (pinfunction "1_1") (pintype "passive"))
      (node (ref "C120") (pin "1") (pinfunction "1_1") (pintype "passive"))
      (node (ref "C121") (pin "1") (pinfunction "1_1") (pintype "passive"))
      (node (ref "C122") (pin "1") (pinfunction "1_1") (pintype "passive"))
      (node (ref "C123") (pin "1") (pinfunction "1_1") (pintype "passive"))
      (node (ref "C124") (pin "1") (pinfunction "1_1") (pintype "passive"))
      (node (ref "C125") (pin "1") (pinfunction "1_1") (pintype "passive"))
      (node (ref "C126") (pin "1") (pinfunction "1_1") (pintype "passive"))
      (node (ref "C127") (pin "1") (pinfunction "1_1") (pintype "passive"))
      (node (ref "C128") (pin "1") (pinfunction "1_1") (pintype "passive"))
      (node (ref "C129") (pin "1") (pinfunction "1_1") (pintype "passive"))
      (node (ref "C130") (pin "1") (pinfunction "1_1") (pintype "passive"))
      (node (ref "C131") (pin "2") (pinfunction "2_2") (pintype "passive"))
      (node (ref "C132") (pin "1") (pinfunction "1_1") (pintype "passive"))
      (node (ref "C133") (pin "1") (pinfunction "1_1") (pintype "passive"))
      (node (ref "C134") (pin "2") (pinfunction "2_2") (pintype "passive"))
      (node (ref "C135") (pin "2") (pinfunction "2_2") (pintype "passive"))
      (node (ref "C136") (pin "2") (pinfunction "2_2") (pintype "passive"))
      (node (ref "C137") (pin "2") (pinfunction "2_2") (pintype "passive"))
      (node (ref "C138") (pin "2") (pinfunction "2_2") (pintype "passive"))
      (node (ref "C97") (pin "1") (pinfunction "1_1") (pintype "passive"))
      (node (ref "C98") (pin "1") (pinfunction "1_1") (pintype "passive"))
      (node (ref "C99") (pin "1") (pinfunction "1_1") (pintype "passive"))
      (node (ref "R29") (pin "2") (pinfunction "2_2") (pintype "passive"))
      (node (ref "R30") (pin "2") (pinfunction "2_2") (pintype "passive"))
      (node (ref "R31") (pin "2") (pinfunction "2_2") (pintype "passive"))
      (node (ref "R49") (pin "2") (pinfunction "2_2") (pintype "passive"))
      (node (ref "U3") (pin "A9") (pinfunction "VSS_A9") (pintype "power_in"))
      (node (ref "U3") (pin "B1") (pinfunction "VSSQ_B1") (pintype "power_in"))
      (node (ref "U3") (pin "B3") (pinfunction "VSS_B3") (pintype "power_in"))
      (node (ref "U3") (pin "B9") (pinfunction "VSSQ_B9") (pintype "power_in"))
      (node (ref "U3") (pin "D1") (pinfunction "VSSQ_D1") (pintype "power_in"))
      (node (ref "U3") (pin "D8") (pinfunction "VSSQ_D8") (pintype "power_in"))
      (node (ref "U3") (pin "E1") (pinfunction "VSS_E1") (pintype "power_in"))
      (node (ref "U3") (pin "E2") (pinfunction "VSSQ_E2") (pintype "power_in"))
      (node (ref "U3") (pin "E8") (pinfunction "VSSQ_E8") (pintype "power_in"))
      (node (ref "U3") (pin "F9") (pinfunction "VSSQ_F9") (pintype "power_in"))
      (node (ref "U3") (pin "G1") (pinfunction "VSSQ_G1") (pintype "power_in"))
      (node (ref "U3") (pin "G8") (pinfunction "VSS_G8") (pintype "power_in"))
      (node (ref "U3") (pin "G9") (pinfunction "VSSQ_G9") (pintype "power_in"))
      (node (ref "U3") (pin "J2") (pinfunction "VSS_J2") (pintype "power_in"))
      (node (ref "U3") (pin "J8") (pinfunction "VSS_J8") (pintype "power_in"))
      (node (ref "U3") (pin "M1") (pinfunction "VSS_M1") (pintype "power_in"))
      (node (ref "U3") (pin "M9") (pinfunction "VSS_M9") (pintype "power_in"))
      (node (ref "U3") (pin "P1") (pinfunction "VSS_P1") (pintype "power_in"))
      (node (ref "U3") (pin "P9") (pinfunction "VSS_P9") (pintype "power_in"))
      (node (ref "U3") (pin "T1") (pinfunction "VSS_T1") (pintype "power_in"))
      (node (ref "U3") (pin "T9") (pinfunction "VSS_T9") (pintype "power_in"))
      (node (ref "U4") (pin "A9") (pinfunction "VSS_A9") (pintype "power_in"))
      (node (ref "U4") (pin "B1") (pinfunction "VSSQ_B1") (pintype "power_in"))
      (node (ref "U4") (pin "B3") (pinfunction "VSS_B3") (pintype "power_in"))
      (node (ref "U4") (pin "B9") (pinfunction "VSSQ_B9") (pintype "power_in"))
      (node (ref "U4") (pin "D1") (pinfunction "VSSQ_D1") (pintype "power_in"))
      (node (ref "U4") (pin "D8") (pinfunction "VSSQ_D8") (pintype "power_in"))
      (node (ref "U4") (pin "E1") (pinfunction "VSS_E1") (pintype "power_in"))
      (node (ref "U4") (pin "E2") (pinfunction "VSSQ_E2") (pintype "power_in"))
      (node (ref "U4") (pin "E8") (pinfunction "VSSQ_E8") (pintype "power_in"))
      (node (ref "U4") (pin "F9") (pinfunction "VSSQ_F9") (pintype "power_in"))
      (node (ref "U4") (pin "G1") (pinfunction "VSSQ_G1") (pintype "power_in"))
      (node (ref "U4") (pin "G8") (pinfunction "VSS_G8") (pintype "power_in"))
      (node (ref "U4") (pin "G9") (pinfunction "VSSQ_G9") (pintype "power_in"))
      (node (ref "U4") (pin "J2") (pinfunction "VSS_J2") (pintype "power_in"))
      (node (ref "U4") (pin "J8") (pinfunction "VSS_J8") (pintype "power_in"))
      (node (ref "U4") (pin "M1") (pinfunction "VSS_M1") (pintype "power_in"))
      (node (ref "U4") (pin "M9") (pinfunction "VSS_M9") (pintype "power_in"))
      (node (ref "U4") (pin "P1") (pinfunction "VSS_P1") (pintype "power_in"))
      (node (ref "U4") (pin "P9") (pinfunction "VSS_P9") (pintype "power_in"))
      (node (ref "U4") (pin "T1") (pinfunction "VSS_T1") (pintype "power_in"))
      (node (ref "U4") (pin "T9") (pinfunction "VSS_T9") (pintype "power_in"))
      (node (ref "U5") (pin "11") (pinfunction "TP_11") (pintype "passive"))
      (node (ref "U5") (pin "4") (pinfunction "PGND_4") (pintype "passive"))
      (node (ref "U5") (pin "8") (pinfunction "G_8") (pintype "passive"))
    )
    (net (code "79") (name "Net-(U3-ZQ)") (class "Default")
      (node (ref "R29") (pin "1") (pinfunction "1_1") (pintype "passive"))
      (node (ref "U3") (pin "L8") (pinfunction "ZQ_L8") (pintype "passive"))
    )
    (net (code "80") (name "Net-(U4-ZQ)") (class "Default")
      (node (ref "R49") (pin "1") (pinfunction "1_1") (pintype "passive"))
      (node (ref "U4") (pin "L8") (pinfunction "ZQ_L8") (pintype "passive"))
    )
    (net (code "81") (name "Net-(U5-S3)") (class "Default")
      (node (ref "R50") (pin "2") (pinfunction "2_2") (pintype "passive"))
      (node (ref "R54") (pin "2") (pinfunction "2_2") (pintype "passive"))
      (node (ref "U5") (pin "7") (pinfunction "S3_7") (pintype "passive"))
      (node (ref "U5") (pin "9") (pinfunction "S5_9") (pintype "passive"))
    )
    (net (code "82") (name "VCC1V5") (class "Default")
      (node (ref "C100") (pin "2") (pinfunction "2_2") (pintype "passive"))
      (node (ref "C101") (pin "2") (pinfunction "2_2") (pintype "passive"))
      (node (ref "C102") (pin "2") (pinfunction "2_2") (pintype "passive"))
      (node (ref "C103") (pin "2") (pinfunction "2_2") (pintype "passive"))
      (node (ref "C104") (pin "2") (pinfunction "2_2") (pintype "passive"))
      (node (ref "C105") (pin "2") (pinfunction "2_2") (pintype "passive"))
      (node (ref "C106") (pin "2") (pinfunction "2_2") (pintype "passive"))
      (node (ref "C107") (pin "2") (pinfunction "2_2") (pintype "passive"))
      (node (ref "C108") (pin "2") (pinfunction "2_2") (pintype "passive"))
      (node (ref "C109") (pin "2") (pinfunction "2_2") (pintype "passive"))
      (node (ref "C112") (pin "2") (pinfunction "2_2") (pintype "passive"))
      (node (ref "C113") (pin "2") (pinfunction "2_2") (pintype "passive"))
      (node (ref "C114") (pin "2") (pinfunction "2_2") (pintype "passive"))
      (node (ref "C115") (pin "2") (pinfunction "2_2") (pintype "passive"))
      (node (ref "C116") (pin "2") (pinfunction "2_2") (pintype "passive"))
      (node (ref "C117") (pin "2") (pinfunction "2_2") (pintype "passive"))
      (node (ref "C118") (pin "2") (pinfunction "2_2") (pintype "passive"))
      (node (ref "C119") (pin "2") (pinfunction "2_2") (pintype "passive"))
      (node (ref "C120") (pin "2") (pinfunction "2_2") (pintype "passive"))
      (node (ref "C121") (pin "2") (pinfunction "2_2") (pintype "passive"))
      (node (ref "C122") (pin "2") (pinfunction "2_2") (pintype "passive"))
      (node (ref "C123") (pin "2") (pinfunction "2_2") (pintype "passive"))
      (node (ref "C124") (pin "2") (pinfunction "2_2") (pintype "passive"))
      (node (ref "C132") (pin "2") (pinfunction "2_2") (pintype "passive"))
      (node (ref "C97") (pin "2") (pinfunction "2_2") (pintype "passive"))
      (node (ref "C98") (pin "2") (pinfunction "2_2") (pintype "passive"))
      (node (ref "C99") (pin "2") (pinfunction "2_2") (pintype "passive"))
      (node (ref "R54") (pin "1") (pinfunction "1_1") (pintype "passive"))
      (node (ref "U3") (pin "A1") (pinfunction "VDDQ_A1") (pintype "power_in"))
      (node (ref "U3") (pin "A8") (pinfunction "VDDQ_A8") (pintype "power_in"))
      (node (ref "U3") (pin "B2") (pinfunction "VDD_B2") (pintype "power_in"))
      (node (ref "U3") (pin "C1") (pinfunction "VDDQ_C1") (pintype "power_in"))
      (node (ref "U3") (pin "C9") (pinfunction "VDDQ_C9") (pintype "power_in"))
      (node (ref "U3") (pin "D2") (pinfunction "VDDQ_D2") (pintype "power_in"))
      (node (ref "U3") (pin "D9") (pinfunction "VDD_D9") (pintype "power_in"))
      (node (ref "U3") (pin "E9") (pinfunction "VDDQ_E9") (pintype "power_in"))
      (node (ref "U3") (pin "F1") (pinfunction "VDDQ_F1") (pintype "power_in"))
      (node (ref "U3") (pin "G7") (pinfunction "VDD_G7") (pintype "power_in"))
      (node (ref "U3") (pin "H2") (pinfunction "VDDQ_H2") (pintype "power_in"))
      (node (ref "U3") (pin "H9") (pinfunction "VDDQ_H9") (pintype "power_in"))
      (node (ref "U3") (pin "K2") (pinfunction "VDD_K2") (pintype "power_in"))
      (node (ref "U3") (pin "K8") (pinfunction "VDD_K8") (pintype "power_in"))
      (node (ref "U3") (pin "N1") (pinfunction "VDD_N1") (pintype "power_in"))
      (node (ref "U3") (pin "N9") (pinfunction "VDD_N9") (pintype "power_in"))
      (node (ref "U3") (pin "R1") (pinfunction "VDD_R1") (pintype "power_in"))
      (node (ref "U3") (pin "R9") (pinfunction "VDD_R9") (pintype "power_in"))
      (node (ref "U4") (pin "A1") (pinfunction "VDDQ_A1") (pintype "power_in"))
      (node (ref "U4") (pin "A8") (pinfunction "VDDQ_A8") (pintype "power_in"))
      (node (ref "U4") (pin "B2") (pinfunction "VDD_B2") (pintype "power_in"))
      (node (ref "U4") (pin "C1") (pinfunction "VDDQ_C1") (pintype "power_in"))
      (node (ref "U4") (pin "C9") (pinfunction "VDDQ_C9") (pintype "power_in"))
      (node (ref "U4") (pin "D2") (pinfunction "VDDQ_D2") (pintype "power_in"))
      (node (ref "U4") (pin "D9") (pinfunction "VDD_D9") (pintype "power_in"))
      (node (ref "U4") (pin "E9") (pinfunction "VDDQ_E9") (pintype "power_in"))
      (node (ref "U4") (pin "F1") (pinfunction "VDDQ_F1") (pintype "power_in"))
      (node (ref "U4") (pin "G7") (pinfunction "VDD_G7") (pintype "power_in"))
      (node (ref "U4") (pin "H2") (pinfunction "VDDQ_H2") (pintype "power_in"))
      (node (ref "U4") (pin "H9") (pinfunction "VDDQ_H9") (pintype "power_in"))
      (node (ref "U4") (pin "K2") (pinfunction "VDD_K2") (pintype "power_in"))
      (node (ref "U4") (pin "K8") (pinfunction "VDD_K8") (pintype "power_in"))
      (node (ref "U4") (pin "N1") (pinfunction "VDD_N1") (pintype "power_in"))
      (node (ref "U4") (pin "N9") (pinfunction "VDD_N9") (pintype "power_in"))
      (node (ref "U4") (pin "R1") (pinfunction "VDD_R1") (pintype "power_in"))
      (node (ref "U4") (pin "R9") (pinfunction "VDD_R9") (pintype "power_in"))
      (node (ref "U5") (pin "1") (pinfunction "VDQSN_1") (pintype "passive"))
      (node (ref "U5") (pin "2") (pinfunction "VLDOI_2") (pintype "passive"))
    )
    (net (code "83") (name "VCC3V3") (class "Default")
      (node (ref "C131") (pin "1") (pinfunction "1_1") (pintype "passive"))
      (node (ref "U5") (pin "10") (pinfunction "VDD_10") (pintype "passive"))
    )
    (net (code "84") (name "VTT0V75") (class "Default")
      (node (ref "C127") (pin "2") (pinfunction "2_2") (pintype "passive"))
      (node (ref "C128") (pin "2") (pinfunction "2_2") (pintype "passive"))
      (node (ref "C129") (pin "2") (pinfunction "2_2") (pintype "passive"))
      (node (ref "C130") (pin "2") (pinfunction "2_2") (pintype "passive"))
      (node (ref "C133") (pin "2") (pinfunction "2_2") (pintype "passive"))
      (node (ref "C134") (pin "1") (pinfunction "1_1") (pintype "passive"))
      (node (ref "C135") (pin "1") (pinfunction "1_1") (pintype "passive"))
      (node (ref "C136") (pin "1") (pinfunction "1_1") (pintype "passive"))
      (node (ref "C137") (pin "1") (pinfunction "1_1") (pintype "passive"))
      (node (ref "R33") (pin "1") (pinfunction "1_1") (pintype "passive"))
      (node (ref "R34") (pin "1") (pinfunction "1_1") (pintype "passive"))
      (node (ref "R35") (pin "1") (pinfunction "1_1") (pintype "passive"))
      (node (ref "R36") (pin "1") (pinfunction "1_1") (pintype "passive"))
      (node (ref "R37") (pin "1") (pinfunction "1_1") (pintype "passive"))
      (node (ref "R38") (pin "1") (pinfunction "1_1") (pintype "passive"))
      (node (ref "R39") (pin "1") (pinfunction "1_1") (pintype "passive"))
      (node (ref "R40") (pin "1") (pinfunction "1_1") (pintype "passive"))
      (node (ref "R41") (pin "1") (pinfunction "1_1") (pintype "passive"))
      (node (ref "R42") (pin "1") (pinfunction "1_1") (pintype "passive"))
      (node (ref "R43") (pin "1") (pinfunction "1_1") (pintype "passive"))
      (node (ref "R44") (pin "1") (pinfunction "1_1") (pintype "passive"))
      (node (ref "R45") (pin "1") (pinfunction "1_1") (pintype "passive"))
      (node (ref "R46") (pin "1") (pinfunction "1_1") (pintype "passive"))
      (node (ref "R47") (pin "1") (pinfunction "1_1") (pintype "passive"))
      (node (ref "R48") (pin "1") (pinfunction "1_1") (pintype "passive"))
      (node (ref "R51") (pin "1") (pinfunction "1_1") (pintype "passive"))
      (node (ref "R52") (pin "1") (pinfunction "1_1") (pintype "passive"))
      (node (ref "R53") (pin "1") (pinfunction "1_1") (pintype "passive"))
      (node (ref "R55") (pin "1") (pinfunction "1_1") (pintype "passive"))
      (node (ref "R56") (pin "1") (pinfunction "1_1") (pintype "passive"))
      (node (ref "R57") (pin "1") (pinfunction "1_1") (pintype "passive"))
      (node (ref "R58") (pin "1") (pinfunction "1_1") (pintype "passive"))
      (node (ref "R59") (pin "1") (pinfunction "1_1") (pintype "passive"))
      (node (ref "U5") (pin "3") (pinfunction "VTT_3") (pintype "passive"))
      (node (ref "U5") (pin "5") (pinfunction "VTSNS_5") (pintype "passive"))
    )
    (net (code "85") (name "VTTREF") (class "Default")
      (node (ref "C110") (pin "2") (pinfunction "2_2") (pintype "passive"))
      (node (ref "C111") (pin "2") (pinfunction "2_2") (pintype "passive"))
      (node (ref "C125") (pin "2") (pinfunction "2_2") (pintype "passive"))
      (node (ref "C126") (pin "2") (pinfunction "2_2") (pintype "passive"))
      (node (ref "C138") (pin "1") (pinfunction "1_1") (pintype "passive"))
      (node (ref "U3") (pin "H1") (pinfunction "VREFDQ_H1") (pintype "passive"))
      (node (ref "U3") (pin "M8") (pinfunction "VREFCA_M8") (pintype "passive"))
      (node (ref "U4") (pin "H1") (pinfunction "VREFDQ_H1") (pintype "passive"))
      (node (ref "U4") (pin "M8") (pinfunction "VREFCA_M8") (pintype "passive"))
      (node (ref "U5") (pin "6") (pinfunction "VTTREF_6") (pintype "passive"))
    )
    (net (code "86") (name "unconnected-(U3-CKE1-PadJ9)") (class "Default")
      (node (ref "U3") (pin "J9") (pinfunction "CKE1_J9") (pintype "passive"))
    )
    (net (code "87") (name "unconnected-(U3-CS1#-PadL1)") (class "Default")
      (node (ref "U3") (pin "L1") (pinfunction "CS1#_L1") (pintype "passive"))
    )
    (net (code "88") (name "unconnected-(U3-ODT1-PadJ1)") (class "Default")
      (node (ref "U3") (pin "J1") (pinfunction "ODT1_J1") (pintype "passive"))
    )
    (net (code "89") (name "unconnected-(U3-ZQ1-PadL9)") (class "Default")
      (node (ref "U3") (pin "L9") (pinfunction "ZQ1_L9") (pintype "passive"))
    )
    (net (code "90") (name "unconnected-(U4-CKE1-PadJ9)") (class "Default")
      (node (ref "U4") (pin "J9") (pinfunction "CKE1_J9") (pintype "passive"))
    )
    (net (code "91") (name "unconnected-(U4-CS1#-PadL1)") (class "Default")
      (node (ref "U4") (pin "L1") (pinfunction "CS1#_L1") (pintype "passive"))
    )
    (net (code "92") (name "unconnected-(U4-ODT1-PadJ1)") (class "Default")
      (node (ref "U4") (pin "J1") (pinfunction "ODT1_J1") (pintype "passive"))
    )
    (net (code "93") (name "unconnected-(U4-ZQ1-PadL9)") (class "Default")
      (node (ref "U4") (pin "L9") (pinfunction "ZQ1_L9") (pintype "passive"))
    )
  )
)
